# Sheet1.net
KiCad netlist of a schematic drawn in Altium Designer
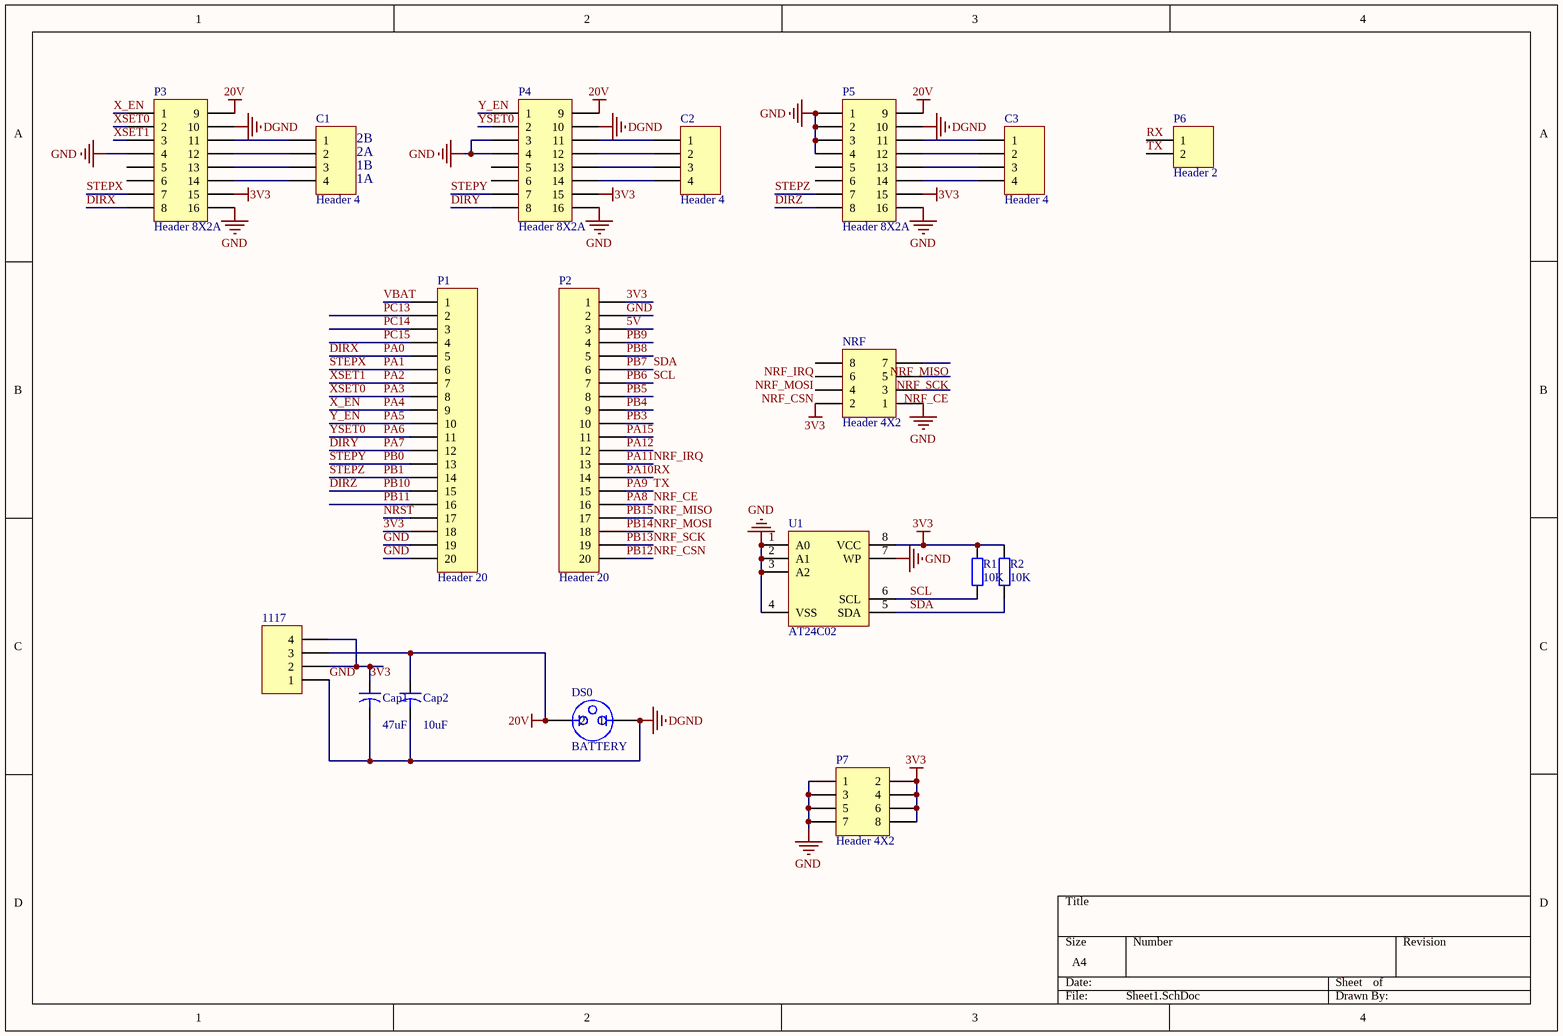
[diagram p0: Sheet1.SchDoc]

(export (version "E")
  (design (tool "Eeschema 10.0.6"))
  (components
    (comp (ref "1117")
      (value "Header 4")
      (footprint "SOT-223")
      (description "Header, 4-Pin")
      (fields (field (name "PUBLISHER") "Altium Limited"))
      (libsource (lib "Miscellaneous Connectors") (part "Header 4"))
    )
    (comp (ref "C1")
      (value "Header 4")
      (footprint "HDR1X4")
      (description "Header, 4-Pin")
      (fields (field (name "PUBLISHER") "Altium Limited"))
      (libsource (lib "") (part "Header 4_1"))
    )
    (comp (ref "C2")
      (value "Header 4")
      (footprint "HDR1X4")
      (description "Header, 4-Pin")
      (fields (field (name "PUBLISHER") "Altium Limited"))
      (libsource (lib "") (part "Header 4_1"))
    )
    (comp (ref "C3")
      (value "Header 4")
      (footprint "HDR1X4")
      (description "Header, 4-Pin")
      (fields (field (name "PUBLISHER") "Altium Limited"))
      (libsource (lib "") (part "Header 4_1"))
    )
    (comp (ref "Cap1")
      (value "47uF")
      (footprint "CAPR5-4X5")
      (description "Capacitor")
      (fields (field (name "Comment") "Cap2") (field (name "PUBLISHER") "Altium Limited"))
      (libsource (lib "Miscellaneous Devices") (part "Cap2"))
    )
    (comp (ref "Cap2")
      (value "10uF")
      (footprint "CAPR5-4X5")
      (description "Capacitor")
      (fields (field (name "Comment") "Cap2") (field (name "PUBLISHER") "Altium Limited"))
      (libsource (lib "Miscellaneous Devices") (part "Cap2"))
    )
    (comp (ref "DS0") (value "BATTERY") (footprint "9V") (libsource (lib "nucleo原理图库") (part "BATTERY")))
    (comp (ref "NRF")
      (value "Header 4X2")
      (footprint "HDR2X4")
      (description "Header, 4-Pin, Dual row")
      (fields (field (name "PUBLISHER") "Altium Limited"))
      (libsource (lib "Miscellaneous Connectors") (part "Header 4X2"))
    )
    (comp (ref "P1")
      (value "Header 20")
      (footprint "HDR1X20")
      (description "Header, 20-Pin")
      (fields (field (name "PUBLISHER") "Altium Limited"))
      (libsource (lib "Miscellaneous Connectors") (part "Header 20"))
    )
    (comp (ref "P2")
      (value "Header 20")
      (footprint "HDR1X20")
      (description "Header, 20-Pin")
      (fields (field (name "PUBLISHER") "Altium Limited"))
      (libsource (lib "") (part "Header 20_1"))
    )
    (comp (ref "P3")
      (value "Header 8X2A")
      (footprint "PCBComponent_1")
      (description "Header, 8-Pin, Dual row")
      (fields (field (name "PUBLISHER") "Altium Limited"))
      (libsource (lib "Miscellaneous Connectors") (part "Header 8X2A"))
    )
    (comp (ref "P4")
      (value "Header 8X2A")
      (footprint "PCBComponent_1")
      (description "Header, 8-Pin, Dual row")
      (fields (field (name "PUBLISHER") "Altium Limited"))
      (libsource (lib "Miscellaneous Connectors") (part "Header 8X2A"))
    )
    (comp (ref "P5")
      (value "Header 8X2A")
      (footprint "PCBComponent_1")
      (description "Header, 8-Pin, Dual row")
      (fields (field (name "PUBLISHER") "Altium Limited"))
      (libsource (lib "Miscellaneous Connectors") (part "Header 8X2A"))
    )
    (comp (ref "P6")
      (value "Header 2")
      (footprint "HDR1X2")
      (description "Header, 2-Pin")
      (fields (field (name "PUBLISHER") "Altium Limited"))
      (libsource (lib "Miscellaneous Connectors") (part "Header 2"))
    )
    (comp (ref "P7")
      (value "Header 4X2")
      (footprint "HDR2X4")
      (description "Header, 4-Pin, Dual row")
      (fields (field (name "PUBLISHER") "Altium Limited"))
      (libsource (lib "") (part "Header 4X2_1"))
    )
    (comp (ref "R1")
      (value "10K")
      (footprint "R1/4")
      (description "Resistor")
      (fields (field (name "Comment") "Res2") (field (name "PUBLISHER") "Altium Limited"))
      (libsource (lib "nucleo原理图库") (part "Res2"))
    )
    (comp (ref "R2")
      (value "10K")
      (footprint "R1/4")
      (description "Resistor")
      (fields (field (name "Comment") "Res2") (field (name "PUBLISHER") "Altium Limited"))
      (libsource (lib "nucleo原理图库") (part "Res2"))
    )
    (comp (ref "U1")
      (value "AT24C02")
      (footprint "SOIC8P")
      (description "EEROM存储器")
      (libsource (lib "nucleo原理图库") (part "AT24C02"))
    )
  )
  (nets
    (net (code "1") (name "/5V") (class "Default")
      (node (ref "P2") (pin "3") (pinfunction "3_3") (pintype "passive"))
    )
    (net (code "2") (name "/DIRX") (class "Default")
      (node (ref "P1") (pin "5") (pinfunction "5_5") (pintype "passive"))
      (node (ref "P3") (pin "8") (pinfunction "8_8") (pintype "passive"))
    )
    (net (code "3") (name "/DIRY") (class "Default")
      (node (ref "P1") (pin "12") (pinfunction "12_12") (pintype "passive"))
      (node (ref "P4") (pin "8") (pinfunction "8_8") (pintype "passive"))
    )
    (net (code "4") (name "/DIRZ") (class "Default")
      (node (ref "P1") (pin "15") (pinfunction "15_15") (pintype "passive"))
      (node (ref "P5") (pin "8") (pinfunction "8_8") (pintype "passive"))
    )
    (net (code "5") (name "/NRF_CE") (class "Default")
      (node (ref "NRF") (pin "3") (pinfunction "3_3") (pintype "passive"))
      (node (ref "P2") (pin "16") (pinfunction "16_16") (pintype "passive"))
    )
    (net (code "6") (name "/NRF_CSN") (class "Default")
      (node (ref "NRF") (pin "4") (pinfunction "4_4") (pintype "passive"))
      (node (ref "P2") (pin "20") (pinfunction "20_20") (pintype "passive"))
    )
    (net (code "7") (name "/NRF_IRQ") (class "Default")
      (node (ref "NRF") (pin "8") (pinfunction "8_8") (pintype "passive"))
      (node (ref "P2") (pin "13") (pinfunction "13_13") (pintype "passive"))
    )
    (net (code "8") (name "/NRF_MISO") (class "Default")
      (node (ref "NRF") (pin "7") (pinfunction "7_7") (pintype "passive"))
      (node (ref "P2") (pin "17") (pinfunction "17_17") (pintype "passive"))
    )
    (net (code "9") (name "/NRF_MOSI") (class "Default")
      (node (ref "NRF") (pin "6") (pinfunction "6_6") (pintype "passive"))
      (node (ref "P2") (pin "18") (pinfunction "18_18") (pintype "passive"))
    )
    (net (code "10") (name "/NRF_SCK") (class "Default")
      (node (ref "NRF") (pin "5") (pinfunction "5_5") (pintype "passive"))
      (node (ref "P2") (pin "19") (pinfunction "19_19") (pintype "passive"))
    )
    (net (code "11") (name "/NRST") (class "Default")
      (node (ref "P1") (pin "17") (pinfunction "17_17") (pintype "passive"))
    )
    (net (code "12") (name "/PA1") (class "Default")
      (node (ref "P1") (pin "6") (pinfunction "6_6") (pintype "passive"))
      (node (ref "P3") (pin "7") (pinfunction "7_7") (pintype "passive"))
    )
    (net (code "13") (name "/PA2") (class "Default")
      (node (ref "P1") (pin "7") (pinfunction "7_7") (pintype "passive"))
      (node (ref "P3") (pin "3") (pinfunction "3_3") (pintype "passive"))
    )
    (net (code "14") (name "/PA3") (class "Default")
      (node (ref "P1") (pin "8") (pinfunction "8_8") (pintype "passive"))
      (node (ref "P3") (pin "2") (pinfunction "2_2") (pintype "passive"))
    )
    (net (code "15") (name "/PA4") (class "Default")
      (node (ref "P1") (pin "9") (pinfunction "9_9") (pintype "passive"))
      (node (ref "P3") (pin "1") (pinfunction "1_1") (pintype "passive"))
    )
    (net (code "16") (name "/PA5") (class "Default")
      (node (ref "P1") (pin "10") (pinfunction "10_10") (pintype "passive"))
      (node (ref "P4") (pin "1") (pinfunction "1_1") (pintype "passive"))
    )
    (net (code "17") (name "/PA6") (class "Default")
      (node (ref "P1") (pin "11") (pinfunction "11_11") (pintype "passive"))
      (node (ref "P4") (pin "2") (pinfunction "2_2") (pintype "passive"))
    )
    (net (code "18") (name "/PA9") (class "Default")
      (node (ref "P2") (pin "15") (pinfunction "15_15") (pintype "passive"))
      (node (ref "P6") (pin "2") (pinfunction "2_2") (pintype "passive"))
    )
    (net (code "19") (name "/PA10") (class "Default")
      (node (ref "P2") (pin "14") (pinfunction "14_14") (pintype "passive"))
      (node (ref "P6") (pin "1") (pinfunction "1_1") (pintype "passive"))
    )
    (net (code "20") (name "/PA12") (class "Default")
      (node (ref "P2") (pin "12") (pinfunction "12_12") (pintype "passive"))
    )
    (net (code "21") (name "/PA15") (class "Default")
      (node (ref "P2") (pin "11") (pinfunction "11_11") (pintype "passive"))
    )
    (net (code "22") (name "/PB0") (class "Default")
      (node (ref "P1") (pin "13") (pinfunction "13_13") (pintype "passive"))
      (node (ref "P4") (pin "7") (pinfunction "7_7") (pintype "passive"))
    )
    (net (code "23") (name "/PB1") (class "Default")
      (node (ref "P1") (pin "14") (pinfunction "14_14") (pintype "passive"))
      (node (ref "P5") (pin "7") (pinfunction "7_7") (pintype "passive"))
    )
    (net (code "24") (name "/PB3") (class "Default")
      (node (ref "P2") (pin "10") (pinfunction "10_10") (pintype "passive"))
    )
    (net (code "25") (name "/PB4") (class "Default")
      (node (ref "P2") (pin "9") (pinfunction "9_9") (pintype "passive"))
    )
    (net (code "26") (name "/PB5") (class "Default")
      (node (ref "P2") (pin "8") (pinfunction "8_8") (pintype "passive"))
    )
    (net (code "27") (name "/PB6") (class "Default")
      (node (ref "P2") (pin "7") (pinfunction "7_7") (pintype "passive"))
      (node (ref "R1") (pin "1") (pinfunction "1_1") (pintype "passive"))
      (node (ref "U1") (pin "6") (pinfunction "SCL_6") (pintype "passive"))
    )
    (net (code "28") (name "/PB7") (class "Default")
      (node (ref "P2") (pin "6") (pinfunction "6_6") (pintype "passive"))
      (node (ref "R2") (pin "1") (pinfunction "1_1") (pintype "passive"))
      (node (ref "U1") (pin "5") (pinfunction "SDA_5") (pintype "passive"))
    )
    (net (code "29") (name "/PB8") (class "Default")
      (node (ref "P2") (pin "5") (pinfunction "5_5") (pintype "passive"))
    )
    (net (code "30") (name "/PB9") (class "Default")
      (node (ref "P2") (pin "4") (pinfunction "4_4") (pintype "passive"))
    )
    (net (code "31") (name "/PB11") (class "Default")
      (node (ref "P1") (pin "16") (pinfunction "16_16") (pintype "passive"))
    )
    (net (code "32") (name "/PC13") (class "Default")
      (node (ref "P1") (pin "2") (pinfunction "2_2") (pintype "passive"))
    )
    (net (code "33") (name "/PC14") (class "Default")
      (node (ref "P1") (pin "3") (pinfunction "3_3") (pintype "passive"))
    )
    (net (code "34") (name "/PC15") (class "Default")
      (node (ref "P1") (pin "4") (pinfunction "4_4") (pintype "passive"))
    )
    (net (code "35") (name "/VBAT") (class "Default")
      (node (ref "P1") (pin "1") (pinfunction "1_1") (pintype "passive"))
    )
    (net (code "36") (name "3V3") (class "Default")
      (node (ref "1117") (pin "2") (pinfunction "2_2") (pintype "passive"))
      (node (ref "1117") (pin "4") (pinfunction "4_4") (pintype "passive"))
      (node (ref "Cap1") (pin "1") (pinfunction "1_1") (pintype "passive"))
      (node (ref "NRF") (pin "2") (pinfunction "2_2") (pintype "passive"))
      (node (ref "P1") (pin "18") (pinfunction "18_18") (pintype "passive"))
      (node (ref "P2") (pin "1") (pinfunction "1_1") (pintype "passive"))
      (node (ref "P3") (pin "15") (pinfunction "15_15") (pintype "passive"))
      (node (ref "P4") (pin "15") (pinfunction "15_15") (pintype "passive"))
      (node (ref "P5") (pin "15") (pinfunction "15_15") (pintype "passive"))
      (node (ref "P7") (pin "2") (pinfunction "2_2") (pintype "passive"))
      (node (ref "P7") (pin "4") (pinfunction "4_4") (pintype "passive"))
      (node (ref "P7") (pin "6") (pinfunction "6_6") (pintype "passive"))
      (node (ref "P7") (pin "8") (pinfunction "8_8") (pintype "passive"))
      (node (ref "R1") (pin "2") (pinfunction "2_2") (pintype "passive"))
      (node (ref "R2") (pin "2") (pinfunction "2_2") (pintype "passive"))
      (node (ref "U1") (pin "8") (pinfunction "VCC_8") (pintype "passive"))
    )
    (net (code "37") (name "20V") (class "Default")
      (node (ref "1117") (pin "3") (pinfunction "3_3") (pintype "passive"))
      (node (ref "Cap2") (pin "1") (pinfunction "1_1") (pintype "passive"))
      (node (ref "DS0") (pin "2") (pinfunction "2_2") (pintype "passive"))
      (node (ref "P3") (pin "9") (pinfunction "9_9") (pintype "passive"))
      (node (ref "P4") (pin "9") (pinfunction "9_9") (pintype "passive"))
      (node (ref "P5") (pin "9") (pinfunction "9_9") (pintype "passive"))
    )
    (net (code "38") (name "DGND") (class "Default")
      (node (ref "1117") (pin "1") (pinfunction "1_1") (pintype "passive"))
      (node (ref "Cap1") (pin "2") (pinfunction "2_2") (pintype "passive"))
      (node (ref "Cap2") (pin "2") (pinfunction "2_2") (pintype "passive"))
      (node (ref "DS0") (pin "1") (pinfunction "1_1") (pintype "passive"))
      (node (ref "NRF") (pin "1") (pinfunction "1_1") (pintype "passive"))
      (node (ref "P1") (pin "19") (pinfunction "19_19") (pintype "passive"))
      (node (ref "P1") (pin "20") (pinfunction "20_20") (pintype "passive"))
      (node (ref "P2") (pin "2") (pinfunction "2_2") (pintype "passive"))
      (node (ref "P3") (pin "10") (pinfunction "10_10") (pintype "passive"))
      (node (ref "P3") (pin "16") (pinfunction "16_16") (pintype "passive"))
      (node (ref "P3") (pin "4") (pinfunction "4_4") (pintype "passive"))
      (node (ref "P4") (pin "10") (pinfunction "10_10") (pintype "passive"))
      (node (ref "P4") (pin "16") (pinfunction "16_16") (pintype "passive"))
      (node (ref "P4") (pin "3") (pinfunction "3_3") (pintype "passive"))
      (node (ref "P4") (pin "4") (pinfunction "4_4") (pintype "passive"))
      (node (ref "P5") (pin "1") (pinfunction "1_1") (pintype "passive"))
      (node (ref "P5") (pin "10") (pinfunction "10_10") (pintype "passive"))
      (node (ref "P5") (pin "16") (pinfunction "16_16") (pintype "passive"))
      (node (ref "P5") (pin "2") (pinfunction "2_2") (pintype "passive"))
      (node (ref "P5") (pin "3") (pinfunction "3_3") (pintype "passive"))
      (node (ref "P5") (pin "4") (pinfunction "4_4") (pintype "passive"))
      (node (ref "P7") (pin "1") (pinfunction "1_1") (pintype "passive"))
      (node (ref "P7") (pin "3") (pinfunction "3_3") (pintype "passive"))
      (node (ref "P7") (pin "5") (pinfunction "5_5") (pintype "passive"))
      (node (ref "P7") (pin "7") (pinfunction "7_7") (pintype "passive"))
      (node (ref "U1") (pin "1") (pinfunction "A0_1") (pintype "passive"))
      (node (ref "U1") (pin "2") (pinfunction "A1_2") (pintype "passive"))
      (node (ref "U1") (pin "3") (pinfunction "A2_3") (pintype "passive"))
      (node (ref "U1") (pin "4") (pinfunction "VSS_4") (pintype "passive"))
      (node (ref "U1") (pin "7") (pinfunction "WP_7") (pintype "passive"))
    )
    (net (code "39") (name "Net-(C1-Pad1)") (class "Default")
      (node (ref "C1") (pin "1") (pinfunction "1_1") (pintype "passive"))
      (node (ref "P3") (pin "11") (pinfunction "11_11") (pintype "passive"))
    )
    (net (code "40") (name "Net-(C1-Pad2)") (class "Default")
      (node (ref "C1") (pin "2") (pinfunction "2_2") (pintype "passive"))
      (node (ref "P3") (pin "12") (pinfunction "12_12") (pintype "passive"))
    )
    (net (code "41") (name "Net-(C1-Pad3)") (class "Default")
      (node (ref "C1") (pin "3") (pinfunction "3_3") (pintype "passive"))
      (node (ref "P3") (pin "13") (pinfunction "13_13") (pintype "passive"))
    )
    (net (code "42") (name "Net-(C1-Pad4)") (class "Default")
      (node (ref "C1") (pin "4") (pinfunction "4_4") (pintype "passive"))
      (node (ref "P3") (pin "14") (pinfunction "14_14") (pintype "passive"))
    )
    (net (code "43") (name "Net-(C2-Pad1)") (class "Default")
      (node (ref "C2") (pin "1") (pinfunction "1_1") (pintype "passive"))
      (node (ref "P4") (pin "11") (pinfunction "11_11") (pintype "passive"))
    )
    (net (code "44") (name "Net-(C2-Pad2)") (class "Default")
      (node (ref "C2") (pin "2") (pinfunction "2_2") (pintype "passive"))
      (node (ref "P4") (pin "12") (pinfunction "12_12") (pintype "passive"))
    )
    (net (code "45") (name "Net-(C2-Pad3)") (class "Default")
      (node (ref "C2") (pin "3") (pinfunction "3_3") (pintype "passive"))
      (node (ref "P4") (pin "13") (pinfunction "13_13") (pintype "passive"))
    )
    (net (code "46") (name "Net-(C2-Pad4)") (class "Default")
      (node (ref "C2") (pin "4") (pinfunction "4_4") (pintype "passive"))
      (node (ref "P4") (pin "14") (pinfunction "14_14") (pintype "passive"))
    )
    (net (code "47") (name "Net-(C3-Pad1)") (class "Default")
      (node (ref "C3") (pin "1") (pinfunction "1_1") (pintype "passive"))
      (node (ref "P5") (pin "11") (pinfunction "11_11") (pintype "passive"))
    )
    (net (code "48") (name "Net-(C3-Pad2)") (class "Default")
      (node (ref "C3") (pin "2") (pinfunction "2_2") (pintype "passive"))
      (node (ref "P5") (pin "12") (pinfunction "12_12") (pintype "passive"))
    )
    (net (code "49") (name "Net-(C3-Pad3)") (class "Default")
      (node (ref "C3") (pin "3") (pinfunction "3_3") (pintype "passive"))
      (node (ref "P5") (pin "13") (pinfunction "13_13") (pintype "passive"))
    )
    (net (code "50") (name "Net-(C3-Pad4)") (class "Default")
      (node (ref "C3") (pin "4") (pinfunction "4_4") (pintype "passive"))
      (node (ref "P5") (pin "14") (pinfunction "14_14") (pintype "passive"))
    )
    (net (code "51") (name "unconnected-(P3-Pad5)") (class "Default")
      (node (ref "P3") (pin "5") (pinfunction "5_5") (pintype "passive"))
    )
    (net (code "52") (name "unconnected-(P3-Pad6)") (class "Default")
      (node (ref "P3") (pin "6") (pinfunction "6_6") (pintype "passive"))
    )
    (net (code "53") (name "unconnected-(P4-Pad5)") (class "Default")
      (node (ref "P4") (pin "5") (pinfunction "5_5") (pintype "passive"))
    )
    (net (code "54") (name "unconnected-(P4-Pad6)") (class "Default")
      (node (ref "P4") (pin "6") (pinfunction "6_6") (pintype "passive"))
    )
    (net (code "55") (name "unconnected-(P5-Pad5)") (class "Default")
      (node (ref "P5") (pin "5") (pinfunction "5_5") (pintype "passive"))
    )
    (net (code "56") (name "unconnected-(P5-Pad6)") (class "Default")
      (node (ref "P5") (pin "6") (pinfunction "6_6") (pintype "passive"))
    )
  )
)
